# Relay_Analog.net
KiCad netlist of a schematic drawn in Altium Designer
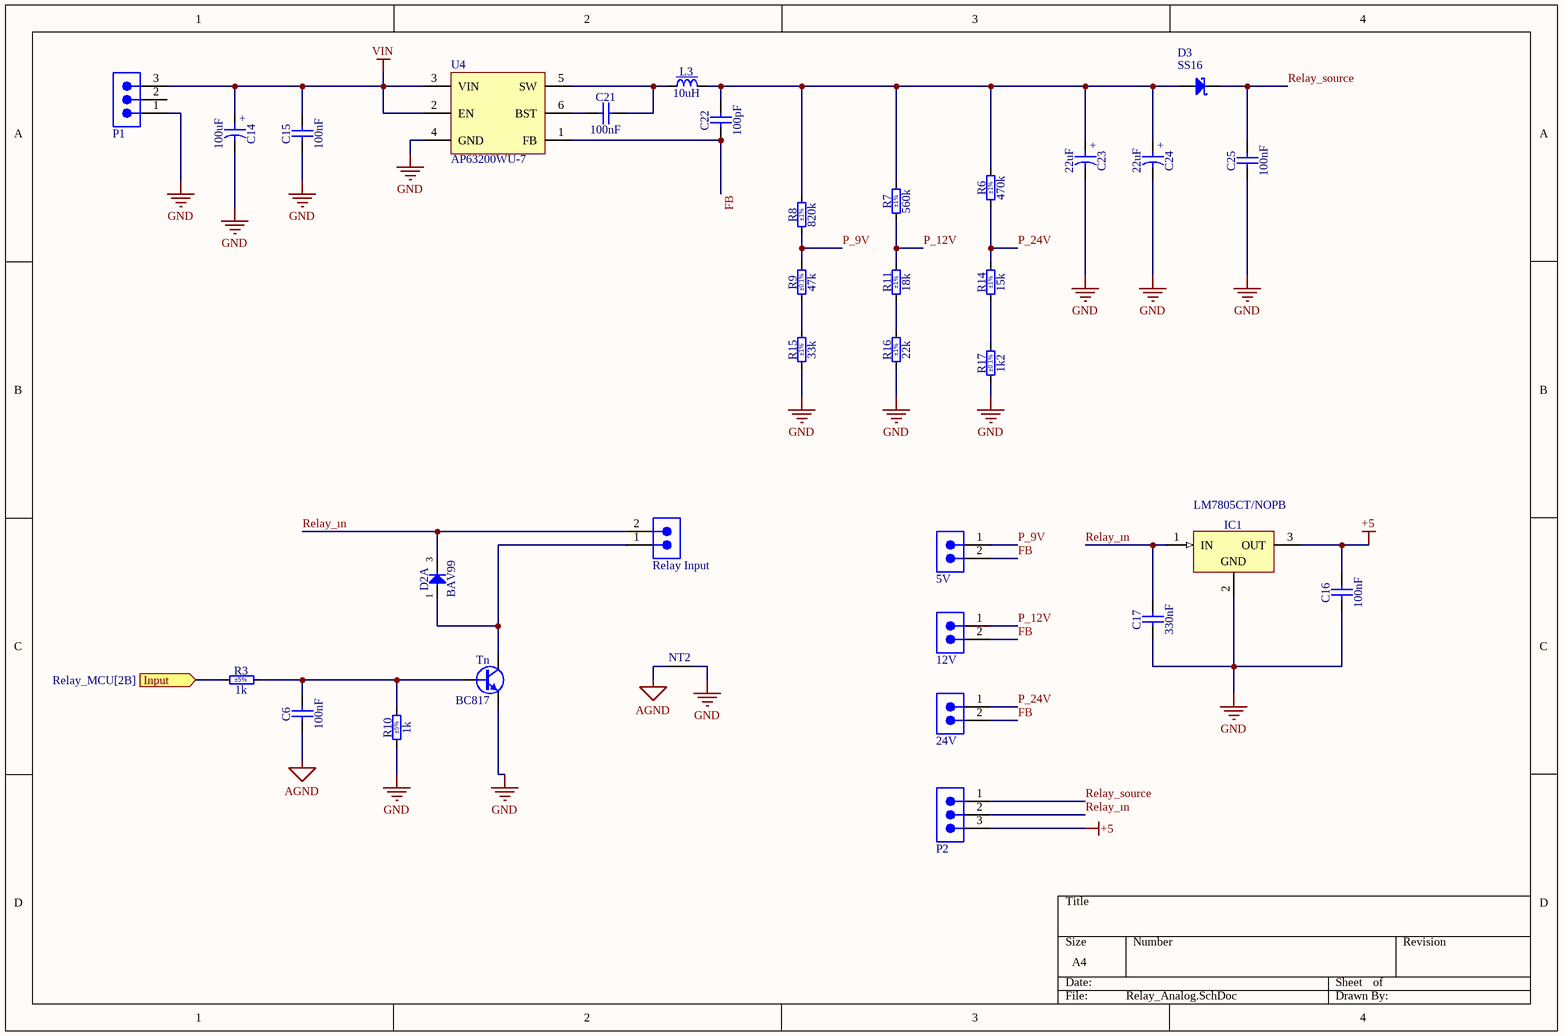
[diagram p0: Relay_Analog.SchDoc]

(export (version "E")
  (design (tool "Eeschema 10.0.6"))
  (components
    (comp (ref "5V")
      (value "61300211121")
      (footprint "61300211121")
      (description "WR-PHD Pin Header, THT, Vertical, pitch 2.54mm, 1 Row, 2P")
      (fields (field (name "MANUFACTURER") "Wurth Elektronik"))
      (libsource (lib "Altium_WR-PHD (rev24a)") (part "61300211121"))
    )
    (comp (ref "12V")
      (value "61300211121")
      (footprint "61300211121")
      (description "WR-PHD Pin Header, THT, Vertical, pitch 2.54mm, 1 Row, 2P")
      (fields (field (name "MANUFACTURER") "Wurth Elektronik"))
      (libsource (lib "Altium_WR-PHD (rev24a)") (part "61300211121"))
    )
    (comp (ref "24V")
      (value "61300211121")
      (footprint "61300211121")
      (description "WR-PHD Pin Header, THT, Vertical, pitch 2.54mm, 1 Row, 2P")
      (fields (field (name "MANUFACTURER") "Wurth Elektronik"))
      (libsource (lib "Altium_WR-PHD (rev24a)") (part "61300211121"))
    )
    (comp (ref "C6")
      (value "100nF")
      (footprint "CAPC2012X135N")
      (description "Non-polarised capacitor")
      (fields
        (field (name "PART NUMBER") "CC0805_100NF_50V_10%_X7R")
        (field (name "VOLTAGE") "50V")
        (field (name "AUTHOR") "CERN DEM JLC")
      )
      (libsource (lib "Capacitors") (part "Capacitor - non polarized"))
    )
    (comp (ref "C14")
      (value "100uF")
      (footprint "CAPPR250-680X1250")
      (description "Polarised capacitor")
      (fields
        (field (name "PART NUMBER") "CAER_100UF_25V_20%_NICHICON_UPS1E101MED")
        (field (name "VOLTAGE") "25V")
        (field (name "AUTHOR") "CERN DEM MR")
      )
      (libsource (lib "Capacitors") (part "Capacitor - polarized"))
    )
    (comp (ref "C15")
      (value "100nF")
      (footprint "CAPC2012X135N")
      (description "Non-polarised capacitor")
      (fields
        (field (name "PART NUMBER") "CC0805_100NF_50V_10%_X7R")
        (field (name "VOLTAGE") "50V")
        (field (name "AUTHOR") "CERN DEM JLC")
      )
      (libsource (lib "Capacitors") (part "Capacitor - non polarized"))
    )
    (comp (ref "C16")
      (value "100nF")
      (footprint "CAPC2012X135N")
      (description "Non-polarised capacitor")
      (fields
        (field (name "PART NUMBER") "CC0805_100NF_50V_10%_X7R")
        (field (name "VOLTAGE") "50V")
        (field (name "AUTHOR") "CERN DEM JLC")
      )
      (libsource (lib "Capacitors") (part "Capacitor - non polarized"))
    )
    (comp (ref "C17")
      (value "330nF")
      (footprint "CAPC2012X135N")
      (description "Non-polarised capacitor")
      (fields
        (field (name "PART NUMBER") "CC0805_330NF_16V_10%_X7R")
        (field (name "VOLTAGE") "16V")
        (field (name "AUTHOR") "CERN DEM JLC")
      )
      (libsource (lib "Capacitors") (part "Capacitor - non polarized"))
    )
    (comp (ref "C21")
      (value "100nF")
      (footprint "CAPC2012X135N")
      (description "Non-polarised capacitor")
      (fields
        (field (name "PART NUMBER") "CC0805_100NF_50V_10%_X7R")
        (field (name "VOLTAGE") "50V")
        (field (name "AUTHOR") "CERN DEM JLC")
      )
      (libsource (lib "Capacitors") (part "Capacitor - non polarized"))
    )
    (comp (ref "C22")
      (value "100pF")
      (footprint "CAPC2012X135N")
      (description "Non-polarised capacitor")
      (fields
        (field (name "PART NUMBER") "CC0805_100PF_50V_5%_NP0")
        (field (name "VOLTAGE") "50V")
        (field (name "AUTHOR") "CERN DEM JLC")
      )
      (libsource (lib "Capacitors") (part "Capacitor - non polarized"))
    )
    (comp (ref "C23")
      (value "22uF")
      (footprint "CAPPR250-500X1100")
      (description "Polarised capacitor")
      (fields
        (field (name "PART NUMBER") "CAER_22UF_25V_20%_250-500X1100")
        (field (name "VOLTAGE") "25V")
        (field (name "AUTHOR") "CERN DEM JLC")
      )
      (libsource (lib "Capacitors") (part "Capacitor - polarized"))
    )
    (comp (ref "C24")
      (value "22uF")
      (footprint "CAPPR250-500X1100")
      (description "Polarised capacitor")
      (fields
        (field (name "PART NUMBER") "CAER_22UF_25V_20%_250-500X1100")
        (field (name "VOLTAGE") "25V")
        (field (name "AUTHOR") "CERN DEM JLC")
      )
      (libsource (lib "Capacitors") (part "Capacitor - polarized"))
    )
    (comp (ref "C25")
      (value "100nF")
      (footprint "CAPC2012X135N")
      (description "Non-polarised capacitor")
      (fields
        (field (name "PART NUMBER") "CC0805_100NF_50V_10%_X7R")
        (field (name "VOLTAGE") "50V")
        (field (name "AUTHOR") "CERN DEM JLC")
      )
      (libsource (lib "Capacitors") (part "Capacitor - non polarized"))
    )
    (comp (ref "D2")
      (value "BAV99")
      (footprint "SOT95P240X110-3N")
      (description "Serial Diode")
      (fields
        (field (name "VOLTAGE") "70V")
        (field (name "POWER") "350mW")
        (field (name "AUTHOR") "CERN DEM JLC")
      )
      (libsource (lib "ICs And Semiconductors") (part "Diode x2 A1C3_A3C2"))
    )
    (comp (ref "D3")
      (value "SS16")
      (footprint "DIOM5127X229N")
      (description "Schottky Diode")
      (fields
        (field (name "VOLTAGE") "60V")
        (field (name "POWER") "1A")
        (field (name "AUTHOR") "CERN DEM JLC")
      )
      (libsource (lib "ICs And Semiconductors") (part "Diode Schottky"))
    )
    (comp (ref "IC1")
      (value "LM7805CT/NOPB")
      (footprint "TO-220-V")
      (description "3-Terminal Regulator 1=IN 2=GND 3=OUT")
      (fields
        (field (name "PART NUMBER") "LM7805CT/NOPB_v")
        (field (name "MANUFACTURER") "TEXAS INSTRUMENTS")
        (field (name "AUTHOR") "CERN DEM JLC")
      )
      (libsource (lib "ICs And Semiconductors") (part "REG3 1IN-2GND-3OUT"))
    )
    (comp (ref "L3")
      (value "10uH")
      (footprint "IND_TRACO_TCK-047")
      (description "Inductor With Core")
      (fields
        (field (name "PART NUMBER") "IND_10UH_20%_TRACO_TCK-047")
        (field (name "POWER") "1.44A")
        (field (name "AUTHOR") "CERN DEM JLC")
      )
      (libsource (lib "Inductors & Transformers") (part "Inductor With Magnetic core"))
    )
    (comp (ref "NT2")
      (value "~")
      (footprint "NET-TIE")
      (description "Net Tie")
      (libsource (lib "IKU-LIB") (part "Net Tie"))
    )
    (comp (ref "P1")
      (value "691322310003")
      (footprint "691322310003")
      (description "WR-TBL Series 322 Horizontal PCB Header, THT, pitch 3.81mm, 3p")
      (fields (field (name "MANUFACTURER") "Wurth Elektronik"))
      (libsource (lib "WE - Electromechanical Components") (part "TBL - 1R - 03P - Male"))
    )
    (comp (ref "P2")
      (value "61300311121")
      (footprint "61300311121")
      (description "WR-PHD Pin Header, THT, Vertical, pitch 2.54mm, 1 Row, 3P")
      (fields (field (name "MANUFACTURER") "Wurth Elektronik"))
      (libsource (lib "Altium_WR-PHD (rev24a)") (part "61300311121"))
    )
    (comp (ref "R3")
      (value "1k")
      (footprint "RESC2012X60N")
      (description "Resistor - 5%")
      (fields
        (field (name "TOLERANCE") "±5%")
        (field (name "PART NUMBER") "R0805_1K_5%_0.125W_100PPM")
        (field (name "POWER") "0.125W")
        (field (name "AUTHOR") "CERN DEM JLC")
      )
      (libsource (lib "Resistors") (part "Resistor - 1%"))
    )
    (comp (ref "R6")
      (value "470k")
      (footprint "RESC2012X60N")
      (description "Resistor - 1%")
      (fields
        (field (name "TOLERANCE") "±1%")
        (field (name "PART NUMBER") "R0805_470K_1%_0.125W_100PPM")
        (field (name "POWER") "0.125W")
        (field (name "AUTHOR") "CERN DEM JLC")
      )
      (libsource (lib "Resistors") (part "Resistor - 1%"))
    )
    (comp (ref "R7")
      (value "560k")
      (footprint "RESC2012X60N")
      (description "Resistor - 1%")
      (fields
        (field (name "TOLERANCE") "±1%")
        (field (name "PART NUMBER") "R0805_560K_1%_0.125W_100PPM")
        (field (name "POWER") "0.125W")
        (field (name "AUTHOR") "CERN DEM JLC")
      )
      (libsource (lib "Resistors") (part "Resistor - 1%"))
    )
    (comp (ref "R8")
      (value "820k")
      (footprint "RESC2012X60N")
      (description "Resistor - 1%")
      (fields
        (field (name "TOLERANCE") "±1%")
        (field (name "PART NUMBER") "R0805_820K_1%_0.125W_100PPM")
        (field (name "POWER") "0.125W")
        (field (name "AUTHOR") "CERN DEM JLC")
      )
      (libsource (lib "Resistors") (part "Resistor - 1%"))
    )
    (comp (ref "R9")
      (value "47k")
      (footprint "RESC2012X60N")
      (description "Resistor - 0.1%")
      (fields
        (field (name "TOLERANCE") "±0.1%")
        (field (name "PART NUMBER") "R0805_47K_0.1%_0.125W_25PPM")
        (field (name "POWER") "0.125W")
        (field (name "AUTHOR") "CERN DEM JLC")
      )
      (libsource (lib "Resistors") (part "Resistor - 0.1%"))
    )
    (comp (ref "R10")
      (value "1k")
      (footprint "RESC2012X60N")
      (description "Resistor - 5%")
      (fields
        (field (name "TOLERANCE") "±5%")
        (field (name "PART NUMBER") "R0805_1K_5%_0.125W_100PPM")
        (field (name "POWER") "0.125W")
        (field (name "AUTHOR") "CERN DEM JLC")
      )
      (libsource (lib "Resistors") (part "Resistor - 1%"))
    )
    (comp (ref "R11")
      (value "18k")
      (footprint "RESC2012X60N")
      (description "Resistor - 1%")
      (fields
        (field (name "TOLERANCE") "±1%")
        (field (name "PART NUMBER") "R0805_18K_1%_0.125W_100PPM")
        (field (name "POWER") "0.125W")
        (field (name "AUTHOR") "CERN DEM JLC")
      )
      (libsource (lib "Resistors") (part "Resistor - 1%"))
    )
    (comp (ref "R14")
      (value "15k")
      (footprint "RESC2012X60N")
      (description "Resistor - 1%")
      (fields
        (field (name "TOLERANCE") "±1%")
        (field (name "PART NUMBER") "R0805_15K_1%_0.125W_100PPM")
        (field (name "POWER") "0.125W")
        (field (name "AUTHOR") "CERN DEM JLC")
      )
      (libsource (lib "Resistors") (part "Resistor - 1%"))
    )
    (comp (ref "R15")
      (value "33k")
      (footprint "RESC2012X60N")
      (description "Resistor - 1%")
      (fields
        (field (name "TOLERANCE") "±1%")
        (field (name "PART NUMBER") "R0805_33K_1%_0.125W_100PPM")
        (field (name "POWER") "0.125W")
        (field (name "AUTHOR") "CERN DEM JLC")
      )
      (libsource (lib "Resistors") (part "Resistor - 1%"))
    )
    (comp (ref "R16")
      (value "22k")
      (footprint "RESC2012X60N")
      (description "Resistor - 1%")
      (fields
        (field (name "TOLERANCE") "±1%")
        (field (name "PART NUMBER") "R0805_22K_1%_0.125W_100PPM")
        (field (name "POWER") "0.125W")
        (field (name "AUTHOR") "CERN DEM JLC")
      )
      (libsource (lib "Resistors") (part "Resistor - 1%"))
    )
    (comp (ref "R17")
      (value "1k2")
      (footprint "RESC2013X65N")
      (description "Resistor - 0.1%")
      (fields
        (field (name "TOLERANCE") "±0.1%")
        (field (name "PART NUMBER") "R0805_1K2_0.1%_0.1W_25PPM")
        (field (name "POWER") "0.1W")
        (field (name "AUTHOR") "CERN DEM JMW")
      )
      (libsource (lib "Resistors") (part "Resistor - 0.1%"))
    )
    (comp (ref "Relay Input")
      (value "691322310002")
      (footprint "691322310002")
      (description "WR-TBL Series 322 Horizontal PCB Header, THT, pitch 3.81mm, 2p")
      (fields (field (name "MANUFACTURER") "Wurth Elektronik"))
      (libsource (lib "WE - Electromechanical Components") (part "TBL - 1R - 02P - Male"))
    )
    (comp (ref "Tn")
      (value "BC817")
      (footprint "SOT95P230X110-3N")
      (description "NPN Transistor")
      (fields (field (name "MANUFACTURER") "NXP SEMICONDUCTORS") (field (name "AUTHOR") "CERN DEM JLC"))
      (libsource (lib "ICs And Semiconductors") (part "NPN B1 E2 C3"))
    )
    (comp (ref "U4")
      (value "AP63200WU-7")
      (footprint "TSOT26")
      (description "Switching Regulator")
      (fields (field (name "MANUFACTURER") "Diodes"))
      (libsource (lib "IKU-LIB") (part "AP63200WU-7"))
    )
  )
  (nets
    (net (code "1") (name "+5") (class "Default")
      (node (ref "C16") (pin "2") (pinfunction "2_2") (pintype "passive"))
      (node (ref "IC1") (pin "3") (pinfunction "OUT_3") (pintype "power_in"))
      (node (ref "P2") (pin "3") (pinfunction "3_3") (pintype "passive"))
    )
    (net (code "2") (name "/FB") (class "Default")
      (node (ref "12V") (pin "2") (pinfunction "2_2") (pintype "passive"))
      (node (ref "24V") (pin "2") (pinfunction "2_2") (pintype "passive"))
      (node (ref "5V") (pin "2") (pinfunction "2_2") (pintype "passive"))
      (node (ref "C22") (pin "1") (pinfunction "1_1") (pintype "passive"))
      (node (ref "U4") (pin "1") (pinfunction "FB_1") (pintype "passive"))
    )
    (net (code "3") (name "/Input") (class "Default")
      (node (ref "R3") (pin "1") (pinfunction "1_1") (pintype "passive"))
    )
    (net (code "4") (name "/P_9V") (class "Default")
      (node (ref "5V") (pin "1") (pinfunction "1_1") (pintype "passive"))
      (node (ref "R8") (pin "1") (pinfunction "1_1") (pintype "passive"))
      (node (ref "R9") (pin "2") (pinfunction "2_2") (pintype "passive"))
    )
    (net (code "5") (name "/P_12V") (class "Default")
      (node (ref "12V") (pin "1") (pinfunction "1_1") (pintype "passive"))
      (node (ref "R11") (pin "2") (pinfunction "2_2") (pintype "passive"))
      (node (ref "R7") (pin "1") (pinfunction "1_1") (pintype "passive"))
    )
    (net (code "6") (name "/P_24V") (class "Default")
      (node (ref "24V") (pin "1") (pinfunction "1_1") (pintype "passive"))
      (node (ref "R14") (pin "2") (pinfunction "2_2") (pintype "passive"))
      (node (ref "R6") (pin "1") (pinfunction "1_1") (pintype "passive"))
    )
    (net (code "7") (name "/Relay_source") (class "Default")
      (node (ref "C25") (pin "2") (pinfunction "2_2") (pintype "passive"))
      (node (ref "D3") (pin "1") (pinfunction "C_1") (pintype "passive"))
      (node (ref "P2") (pin "1") (pinfunction "1_1") (pintype "passive"))
    )
    (net (code "8") (name "/Relay_ın") (class "Default")
      (node (ref "C17") (pin "2") (pinfunction "2_2") (pintype "passive"))
      (node (ref "D2") (pin "3") (pinfunction "COMAC_3") (pintype "passive"))
      (node (ref "IC1") (pin "1") (pinfunction "IN_1") (pintype "input"))
      (node (ref "P2") (pin "2") (pinfunction "2_2") (pintype "passive"))
      (node (ref "Relay Input") (pin "2") (pinfunction "2_2") (pintype "passive"))
    )
    (net (code "9") (name "AGND") (class "Default")
      (node (ref "C6") (pin "1") (pinfunction "1_1") (pintype "passive"))
      (node (ref "NT2") (pin "1") (pinfunction "1_1") (pintype "bidirectional"))
    )
    (net (code "10") (name "GND") (class "Default")
      (node (ref "C14") (pin "2") (pinfunction "2_2") (pintype "passive"))
      (node (ref "C15") (pin "1") (pinfunction "1_1") (pintype "passive"))
      (node (ref "C16") (pin "1") (pinfunction "1_1") (pintype "passive"))
      (node (ref "C17") (pin "1") (pinfunction "1_1") (pintype "passive"))
      (node (ref "C23") (pin "2") (pinfunction "2_2") (pintype "passive"))
      (node (ref "C24") (pin "2") (pinfunction "2_2") (pintype "passive"))
      (node (ref "C25") (pin "1") (pinfunction "1_1") (pintype "passive"))
      (node (ref "IC1") (pin "2") (pinfunction "GND_2") (pintype "power_in"))
      (node (ref "NT2") (pin "2") (pinfunction "2_2") (pintype "bidirectional"))
      (node (ref "P1") (pin "1") (pinfunction "1_1") (pintype "passive"))
      (node (ref "R10") (pin "1") (pinfunction "1_1") (pintype "passive"))
      (node (ref "R15") (pin "1") (pinfunction "1_1") (pintype "passive"))
      (node (ref "R16") (pin "1") (pinfunction "1_1") (pintype "passive"))
      (node (ref "R17") (pin "1") (pinfunction "1_1") (pintype "passive"))
      (node (ref "Tn") (pin "2") (pinfunction "E_2") (pintype "passive"))
      (node (ref "U4") (pin "4") (pinfunction "GND_4") (pintype "passive"))
    )
    (net (code "11") (name "Net-(D2A-A)") (class "Default")
      (node (ref "D2") (pin "1") (pinfunction "A_1") (pintype "passive"))
      (node (ref "Relay Input") (pin "1") (pinfunction "1_1") (pintype "passive"))
      (node (ref "Tn") (pin "3") (pinfunction "C_3") (pintype "passive"))
    )
    (net (code "12") (name "Net-(D3-A)") (class "Default")
      (node (ref "C22") (pin "2") (pinfunction "2_2") (pintype "passive"))
      (node (ref "C23") (pin "1") (pinfunction "1_1") (pintype "passive"))
      (node (ref "C24") (pin "1") (pinfunction "1_1") (pintype "passive"))
      (node (ref "D3") (pin "2") (pinfunction "A_2") (pintype "passive"))
      (node (ref "L3") (pin "2") (pinfunction "2_2") (pintype "passive"))
      (node (ref "R6") (pin "2") (pinfunction "2_2") (pintype "passive"))
      (node (ref "R7") (pin "2") (pinfunction "2_2") (pintype "passive"))
      (node (ref "R8") (pin "2") (pinfunction "2_2") (pintype "passive"))
    )
    (net (code "13") (name "Net-(R11-Pad1)") (class "Default")
      (node (ref "R11") (pin "1") (pinfunction "1_1") (pintype "passive"))
      (node (ref "R16") (pin "2") (pinfunction "2_2") (pintype "passive"))
    )
    (net (code "14") (name "Net-(R14-Pad1)") (class "Default")
      (node (ref "R14") (pin "1") (pinfunction "1_1") (pintype "passive"))
      (node (ref "R17") (pin "2") (pinfunction "2_2") (pintype "passive"))
    )
    (net (code "15") (name "Net-(R15-Pad2)") (class "Default")
      (node (ref "R15") (pin "2") (pinfunction "2_2") (pintype "passive"))
      (node (ref "R9") (pin "1") (pinfunction "1_1") (pintype "passive"))
    )
    (net (code "16") (name "Net-(Tn-B)") (class "Default")
      (node (ref "C6") (pin "2") (pinfunction "2_2") (pintype "passive"))
      (node (ref "R10") (pin "2") (pinfunction "2_2") (pintype "passive"))
      (node (ref "R3") (pin "2") (pinfunction "2_2") (pintype "passive"))
      (node (ref "Tn") (pin "1") (pinfunction "B_1") (pintype "passive"))
    )
    (net (code "17") (name "Net-(U4-BST)") (class "Default")
      (node (ref "C21") (pin "1") (pinfunction "1_1") (pintype "passive"))
      (node (ref "U4") (pin "6") (pinfunction "BST_6") (pintype "passive"))
    )
    (net (code "18") (name "Net-(U4-SW)") (class "Default")
      (node (ref "C21") (pin "2") (pinfunction "2_2") (pintype "passive"))
      (node (ref "L3") (pin "1") (pinfunction "1_1") (pintype "passive"))
      (node (ref "U4") (pin "5") (pinfunction "SW_5") (pintype "passive"))
    )
    (net (code "19") (name "VIN") (class "Default")
      (node (ref "C14") (pin "1") (pinfunction "1_1") (pintype "passive"))
      (node (ref "C15") (pin "2") (pinfunction "2_2") (pintype "passive"))
      (node (ref "P1") (pin "3") (pinfunction "3_3") (pintype "passive"))
      (node (ref "U4") (pin "2") (pinfunction "EN_2") (pintype "passive"))
      (node (ref "U4") (pin "3") (pinfunction "VIN_3") (pintype "passive"))
    )
    (net (code "20") (name "unconnected-(P1-Pad2)") (class "Default")
      (node (ref "P1") (pin "2") (pinfunction "2_2") (pintype "passive"))
    )
  )
)
